# JlinkV9mini.net
KiCad netlist of a schematic drawn in Altium Designer
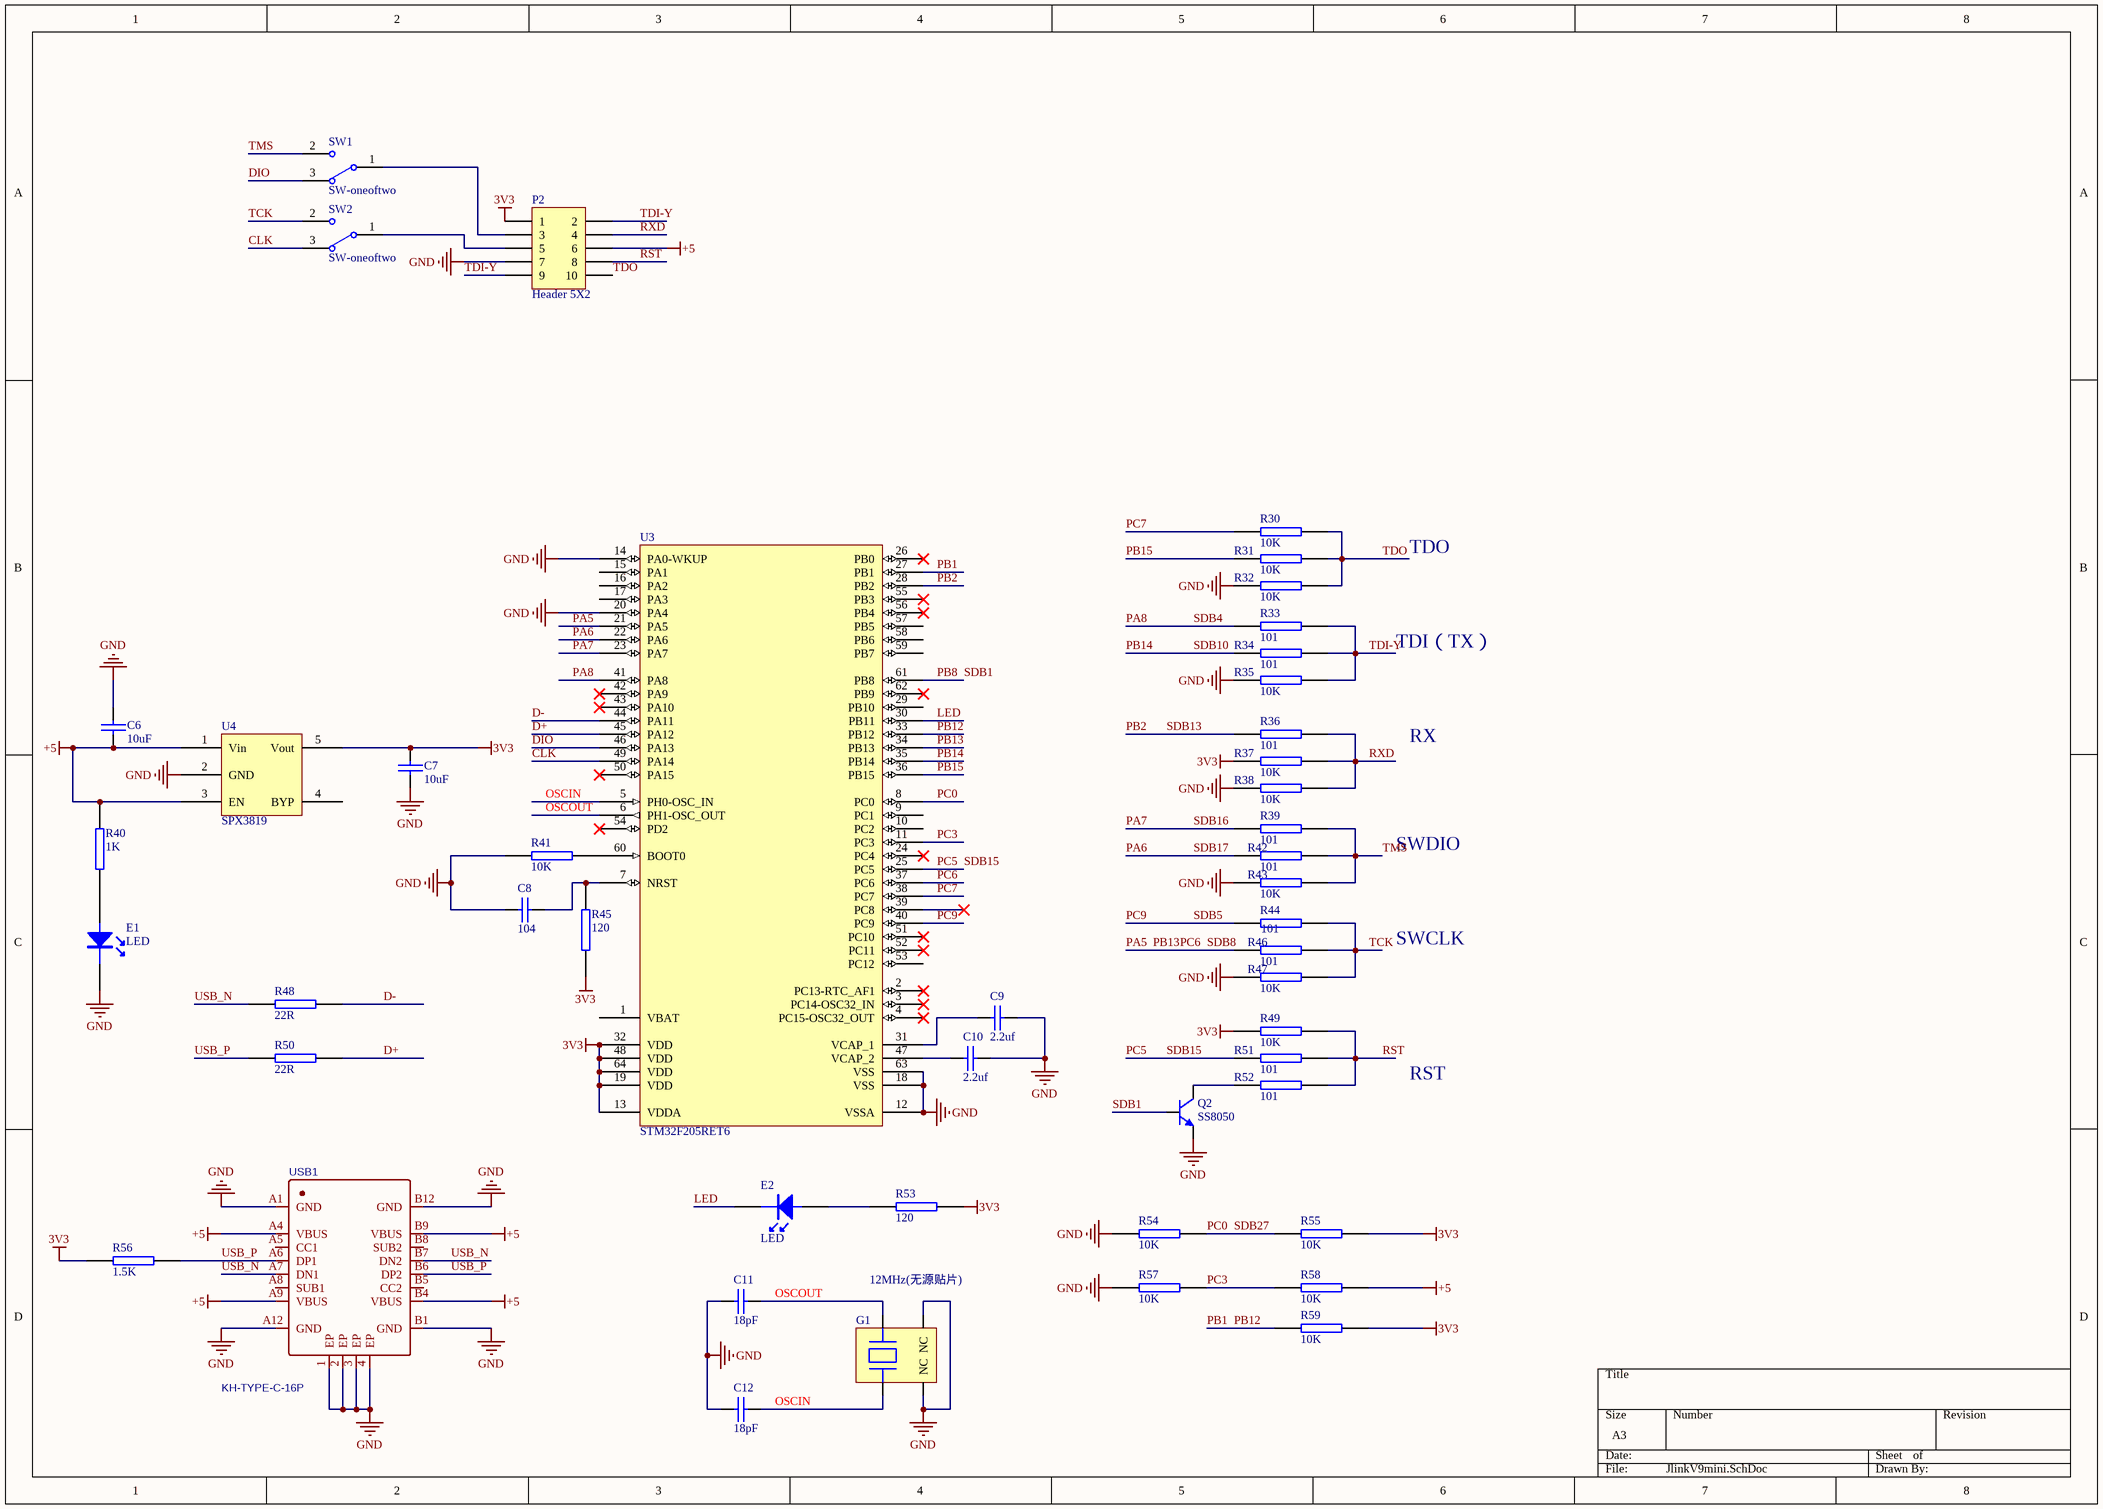
[diagram p0: JlinkV9mini.SchDoc]

(export (version "E")
  (design (tool "Eeschema 10.0.6"))
  (components
    (comp (ref "C6")
      (value "10uF")
      (footprint "0603")
      (description "无极电容")
      (libsource (lib "chenjd") (part "CAP Nonpolarity"))
    )
    (comp (ref "C7")
      (value "10uF")
      (footprint "0603")
      (description "无极电容")
      (libsource (lib "chenjd") (part "CAP Nonpolarity"))
    )
    (comp (ref "C8")
      (value "104")
      (footprint "0603")
      (description "无极电容")
      (libsource (lib "chenjd") (part "CAP Nonpolarity"))
    )
    (comp (ref "C9")
      (value "2.2uf")
      (footprint "0603")
      (description "无极电容")
      (libsource (lib "chenjd") (part "CAP Nonpolarity"))
    )
    (comp (ref "C10")
      (value "2.2uf")
      (footprint "0603")
      (description "无极电容")
      (libsource (lib "chenjd") (part "CAP Nonpolarity"))
    )
    (comp (ref "C11")
      (value "18pF")
      (footprint "0603")
      (description "无极电容")
      (libsource (lib "ZXBC") (part "CAP Nonpolarity"))
    )
    (comp (ref "C12")
      (value "18pF")
      (footprint "0603")
      (description "无极电容")
      (libsource (lib "ZXBC") (part "CAP Nonpolarity"))
    )
    (comp (ref "E1")
      (value "LED")
      (footprint "LED_0603L")
      (description "LED灯")
      (libsource (lib "chenjd") (part "LED"))
    )
    (comp (ref "E2")
      (value "LED")
      (footprint "LED_0603L")
      (description "LED灯")
      (libsource (lib "chenjd") (part "LED"))
    )
    (comp (ref "G1")
      (value "12MHz(无源贴片)")
      (footprint "G3225")
      (description "无源晶振MCU使用")
      (libsource (lib "ZXBC") (part "MM-11B"))
    )
    (comp (ref "P2")
      (value "Header 5X2")
      (footprint "300S-2*5P 2.54MM_2")
      (description "Header, 5-Pin, Dual row")
      (fields (field (name "PUBLISHER") "Altium Limited"))
      (libsource (lib "Miscellaneous Connectors") (part "Header 5X2"))
    )
    (comp (ref "Q2")
      (value "SS8050")
      (footprint "SOT23-3N")
      (description "高频放大-NPN型")
      (fields (field (name "版权归属") "源创客"))
      (libsource (lib "3D库") (part "8050-SMD"))
    )
    (comp (ref "R30")
      (value "10K")
      (footprint "0603")
      (description "电阻")
      (libsource (lib "chenjd") (part "R"))
    )
    (comp (ref "R31")
      (value "10K")
      (footprint "0603")
      (description "电阻")
      (libsource (lib "chenjd") (part "R"))
    )
    (comp (ref "R32")
      (value "10K")
      (footprint "0603")
      (description "电阻")
      (libsource (lib "chenjd") (part "R"))
    )
    (comp (ref "R33")
      (value "101")
      (footprint "0603")
      (description "电阻")
      (libsource (lib "chenjd") (part "R"))
    )
    (comp (ref "R34")
      (value "101")
      (footprint "0603")
      (description "电阻")
      (libsource (lib "chenjd") (part "R"))
    )
    (comp (ref "R35")
      (value "10K")
      (footprint "0603")
      (description "电阻")
      (libsource (lib "chenjd") (part "R"))
    )
    (comp (ref "R36")
      (value "101")
      (footprint "0603")
      (description "电阻")
      (libsource (lib "chenjd") (part "R"))
    )
    (comp (ref "R37")
      (value "10K")
      (footprint "0603")
      (description "电阻")
      (libsource (lib "chenjd") (part "R"))
    )
    (comp (ref "R38")
      (value "10K")
      (footprint "0603")
      (description "电阻")
      (libsource (lib "chenjd") (part "R"))
    )
    (comp (ref "R39")
      (value "101")
      (footprint "0603")
      (description "电阻")
      (libsource (lib "chenjd") (part "R"))
    )
    (comp (ref "R40")
      (value "1K")
      (footprint "0603")
      (description "电阻")
      (libsource (lib "chenjd") (part "R"))
    )
    (comp (ref "R41")
      (value "10K")
      (footprint "0603")
      (description "电阻")
      (libsource (lib "chenjd") (part "R"))
    )
    (comp (ref "R42")
      (value "101")
      (footprint "0603")
      (description "电阻")
      (libsource (lib "chenjd") (part "R"))
    )
    (comp (ref "R43")
      (value "10K")
      (footprint "0603")
      (description "电阻")
      (libsource (lib "chenjd") (part "R"))
    )
    (comp (ref "R44")
      (value "101")
      (footprint "0603")
      (description "电阻")
      (libsource (lib "chenjd") (part "R"))
    )
    (comp (ref "R45")
      (value "120")
      (footprint "0603")
      (description "电阻")
      (libsource (lib "chenjd") (part "R"))
    )
    (comp (ref "R46")
      (value "101")
      (footprint "0603")
      (description "电阻")
      (libsource (lib "chenjd") (part "R"))
    )
    (comp (ref "R47")
      (value "10K")
      (footprint "0603")
      (description "电阻")
      (libsource (lib "chenjd") (part "R"))
    )
    (comp (ref "R48")
      (value "22R")
      (footprint "0603")
      (description "电阻")
      (libsource (lib "chenjd") (part "R"))
    )
    (comp (ref "R49")
      (value "10K")
      (footprint "0603")
      (description "电阻")
      (libsource (lib "chenjd") (part "R"))
    )
    (comp (ref "R50")
      (value "22R")
      (footprint "0603")
      (description "电阻")
      (libsource (lib "chenjd") (part "R"))
    )
    (comp (ref "R51")
      (value "101")
      (footprint "0603")
      (description "电阻")
      (libsource (lib "chenjd") (part "R"))
    )
    (comp (ref "R52")
      (value "101")
      (footprint "0603")
      (description "电阻")
      (libsource (lib "chenjd") (part "R"))
    )
    (comp (ref "R53")
      (value "120")
      (footprint "0603")
      (description "电阻")
      (libsource (lib "chenjd") (part "R"))
    )
    (comp (ref "R54")
      (value "10K")
      (footprint "0603")
      (description "电阻")
      (libsource (lib "chenjd") (part "R"))
    )
    (comp (ref "R55")
      (value "10K")
      (footprint "0603")
      (description "电阻")
      (libsource (lib "chenjd") (part "R"))
    )
    (comp (ref "R56")
      (value "1.5K")
      (footprint "0603")
      (description "电阻")
      (libsource (lib "chenjd") (part "R"))
    )
    (comp (ref "R57")
      (value "10K")
      (footprint "0603")
      (description "电阻")
      (libsource (lib "chenjd") (part "R"))
    )
    (comp (ref "R58")
      (value "10K")
      (footprint "0603")
      (description "电阻")
      (libsource (lib "chenjd") (part "R"))
    )
    (comp (ref "R59")
      (value "10K")
      (footprint "0603")
      (description "电阻")
      (libsource (lib "chenjd") (part "R"))
    )
    (comp (ref "SW1")
      (value "SW-oneoftwo")
      (footprint "SW-oneoftwo-0603")
      (description "二选一电阻开关")
      (libsource (lib "chenjd") (part "SW-oneoftwo"))
    )
    (comp (ref "SW2")
      (value "SW-oneoftwo")
      (footprint "SW-oneoftwo-0603")
      (description "二选一电阻开关")
      (libsource (lib "chenjd") (part "SW-oneoftwo"))
    )
    (comp (ref "U3")
      (value "STM32F205RET6")
      (footprint "LQFP64 10x10_N")
      (description "Microcontroller   ST")
      (libsource (lib "Fantasy") (part "STM32F205RET6"))
    )
    (comp (ref "U4")
      (value "SPX3819")
      (footprint "SOT-23-5")
      (description "稳压器")
      (libsource (lib "chenjd") (part "SPX3819"))
    )
    (comp (ref "USB1")
      (value "KH-TYPE-C-16P")
      (footprint "USB-C-16P")
      (fields (field (name "BOM_SUPPLIER PART") "C709357") (field (name "CONTRIBUTOR") "LCSC"))
      (libsource (lib "chenjd") (part "USB-TYPE-C 16P"))
    )
  )
  (nets
    (net (code "1") (name "+5") (class "Default")
      (node (ref "C6") (pin "2") (pinfunction "2_2") (pintype "passive"))
      (node (ref "P2") (pin "6") (pinfunction "6_6") (pintype "passive"))
      (node (ref "R40") (pin "1") (pinfunction "1_1") (pintype "passive"))
      (node (ref "R58") (pin "2") (pinfunction "2_2") (pintype "passive"))
      (node (ref "U4") (pin "1") (pinfunction "Vin_1") (pintype "passive"))
      (node (ref "U4") (pin "3") (pinfunction "EN_3") (pintype "passive"))
      (node (ref "USB1") (pin "A4") (pinfunction "VBUS_A4") (pintype "passive"))
      (node (ref "USB1") (pin "A9") (pinfunction "VBUS_A9") (pintype "passive"))
      (node (ref "USB1") (pin "B4") (pinfunction "VBUS_B4") (pintype "passive"))
      (node (ref "USB1") (pin "B9") (pinfunction "VBUS_B9") (pintype "passive"))
    )
    (net (code "2") (name "/CLK") (class "Default")
      (node (ref "SW2") (pin "3") (pinfunction "3_3") (pintype "passive"))
      (node (ref "U3") (pin "49") (pinfunction "PA14_49") (pintype "bidirectional"))
    )
    (net (code "3") (name "/D+") (class "Default")
      (node (ref "R50") (pin "1") (pinfunction "1_1") (pintype "passive"))
      (node (ref "U3") (pin "45") (pinfunction "PA12_45") (pintype "bidirectional"))
    )
    (net (code "4") (name "/D-") (class "Default")
      (node (ref "R48") (pin "1") (pinfunction "1_1") (pintype "passive"))
      (node (ref "U3") (pin "44") (pinfunction "PA11_44") (pintype "bidirectional"))
    )
    (net (code "5") (name "/DIO") (class "Default")
      (node (ref "SW1") (pin "3") (pinfunction "3_3") (pintype "passive"))
      (node (ref "U3") (pin "46") (pinfunction "PA13_46") (pintype "bidirectional"))
    )
    (net (code "6") (name "/LED") (class "Default")
      (node (ref "E2") (pin "2") (pinfunction "2_2") (pintype "passive"))
      (node (ref "U3") (pin "30") (pinfunction "PB11_30") (pintype "bidirectional"))
    )
    (net (code "7") (name "/OSCIN") (class "Default")
      (node (ref "C12") (pin "2") (pintype "passive"))
      (node (ref "G1") (pin "1") (pinfunction "1_1") (pintype "passive"))
      (node (ref "U3") (pin "5") (pinfunction "PH0-OSC_IN_5") (pintype "input"))
    )
    (net (code "8") (name "/OSCOUT") (class "Default")
      (node (ref "C11") (pin "2") (pintype "passive"))
      (node (ref "G1") (pin "3") (pinfunction "3_3") (pintype "passive"))
      (node (ref "U3") (pin "6") (pinfunction "PH1-OSC_OUT_6") (pintype "output"))
    )
    (net (code "9") (name "/PA5") (class "Default")
      (node (ref "R46") (pin "1") (pinfunction "1_1") (pintype "passive"))
      (node (ref "U3") (pin "21") (pinfunction "PA5_21") (pintype "bidirectional"))
      (node (ref "U3") (pin "34") (pinfunction "PB13_34") (pintype "bidirectional"))
      (node (ref "U3") (pin "37") (pinfunction "PC6_37") (pintype "bidirectional"))
    )
    (net (code "10") (name "/PA6") (class "Default")
      (node (ref "R42") (pin "1") (pinfunction "1_1") (pintype "passive"))
      (node (ref "U3") (pin "22") (pinfunction "PA6_22") (pintype "bidirectional"))
    )
    (net (code "11") (name "/PA7") (class "Default")
      (node (ref "R39") (pin "1") (pinfunction "1_1") (pintype "passive"))
      (node (ref "U3") (pin "23") (pinfunction "PA7_23") (pintype "bidirectional"))
    )
    (net (code "12") (name "/PA8") (class "Default")
      (node (ref "R33") (pin "1") (pinfunction "1_1") (pintype "passive"))
      (node (ref "U3") (pin "41") (pinfunction "PA8_41") (pintype "bidirectional"))
    )
    (net (code "13") (name "/PB1") (class "Default")
      (node (ref "R59") (pin "1") (pinfunction "1_1") (pintype "passive"))
      (node (ref "U3") (pin "27") (pinfunction "PB1_27") (pintype "bidirectional"))
      (node (ref "U3") (pin "33") (pinfunction "PB12_33") (pintype "bidirectional"))
    )
    (net (code "14") (name "/PB2") (class "Default")
      (node (ref "R36") (pin "1") (pinfunction "1_1") (pintype "passive"))
      (node (ref "U3") (pin "28") (pinfunction "PB2_28") (pintype "bidirectional"))
    )
    (net (code "15") (name "/PB8") (class "Default")
      (node (ref "Q2") (pin "1") (pinfunction "B_1") (pintype "passive"))
      (node (ref "U3") (pin "61") (pinfunction "PB8_61") (pintype "bidirectional"))
    )
    (net (code "16") (name "/PB14") (class "Default")
      (node (ref "R34") (pin "1") (pinfunction "1_1") (pintype "passive"))
      (node (ref "U3") (pin "35") (pinfunction "PB14_35") (pintype "bidirectional"))
    )
    (net (code "17") (name "/PB15") (class "Default")
      (node (ref "R31") (pin "1") (pinfunction "1_1") (pintype "passive"))
      (node (ref "U3") (pin "36") (pinfunction "PB15_36") (pintype "bidirectional"))
    )
    (net (code "18") (name "/PC0") (class "Default")
      (node (ref "R54") (pin "2") (pinfunction "2_2") (pintype "passive"))
      (node (ref "R55") (pin "1") (pinfunction "1_1") (pintype "passive"))
      (node (ref "U3") (pin "8") (pinfunction "PC0_8") (pintype "bidirectional"))
    )
    (net (code "19") (name "/PC3") (class "Default")
      (node (ref "R57") (pin "2") (pinfunction "2_2") (pintype "passive"))
      (node (ref "R58") (pin "1") (pinfunction "1_1") (pintype "passive"))
      (node (ref "U3") (pin "11") (pinfunction "PC3_11") (pintype "bidirectional"))
    )
    (net (code "20") (name "/PC5") (class "Default")
      (node (ref "R51") (pin "1") (pinfunction "1_1") (pintype "passive"))
      (node (ref "U3") (pin "25") (pinfunction "PC5_25") (pintype "bidirectional"))
    )
    (net (code "21") (name "/PC7") (class "Default")
      (node (ref "R30") (pin "1") (pinfunction "1_1") (pintype "passive"))
      (node (ref "U3") (pin "38") (pinfunction "PC7_38") (pintype "bidirectional"))
    )
    (net (code "22") (name "/PC9") (class "Default")
      (node (ref "R44") (pin "1") (pinfunction "1_1") (pintype "passive"))
      (node (ref "U3") (pin "40") (pinfunction "PC9_40") (pintype "bidirectional"))
    )
    (net (code "23") (name "/RST") (class "Default")
      (node (ref "P2") (pin "8") (pinfunction "8_8") (pintype "passive"))
      (node (ref "R49") (pin "2") (pinfunction "2_2") (pintype "passive"))
      (node (ref "R51") (pin "2") (pinfunction "2_2") (pintype "passive"))
      (node (ref "R52") (pin "2") (pinfunction "2_2") (pintype "passive"))
    )
    (net (code "24") (name "/RXD") (class "Default")
      (node (ref "P2") (pin "4") (pinfunction "4_4") (pintype "passive"))
      (node (ref "R36") (pin "2") (pinfunction "2_2") (pintype "passive"))
      (node (ref "R37") (pin "2") (pinfunction "2_2") (pintype "passive"))
      (node (ref "R38") (pin "2") (pinfunction "2_2") (pintype "passive"))
    )
    (net (code "25") (name "/TCK") (class "Default")
      (node (ref "R44") (pin "2") (pinfunction "2_2") (pintype "passive"))
      (node (ref "R46") (pin "2") (pinfunction "2_2") (pintype "passive"))
      (node (ref "R47") (pin "2") (pinfunction "2_2") (pintype "passive"))
      (node (ref "SW2") (pin "2") (pinfunction "2_2") (pintype "passive"))
    )
    (net (code "26") (name "/TDI-Y") (class "Default")
      (node (ref "P2") (pin "2") (pinfunction "2_2") (pintype "passive"))
      (node (ref "P2") (pin "9") (pinfunction "9_9") (pintype "passive"))
      (node (ref "R33") (pin "2") (pinfunction "2_2") (pintype "passive"))
      (node (ref "R34") (pin "2") (pinfunction "2_2") (pintype "passive"))
      (node (ref "R35") (pin "2") (pinfunction "2_2") (pintype "passive"))
    )
    (net (code "27") (name "/TDO") (class "Default")
      (node (ref "P2") (pin "10") (pinfunction "10_10") (pintype "passive"))
      (node (ref "R30") (pin "2") (pinfunction "2_2") (pintype "passive"))
      (node (ref "R31") (pin "2") (pinfunction "2_2") (pintype "passive"))
      (node (ref "R32") (pin "2") (pinfunction "2_2") (pintype "passive"))
    )
    (net (code "28") (name "/TMS") (class "Default")
      (node (ref "R39") (pin "2") (pinfunction "2_2") (pintype "passive"))
      (node (ref "R42") (pin "2") (pinfunction "2_2") (pintype "passive"))
      (node (ref "R43") (pin "2") (pinfunction "2_2") (pintype "passive"))
      (node (ref "SW1") (pin "2") (pinfunction "2_2") (pintype "passive"))
    )
    (net (code "29") (name "/USB_N") (class "Default")
      (node (ref "R48") (pin "2") (pinfunction "2_2") (pintype "passive"))
      (node (ref "USB1") (pin "A7") (pinfunction "DN1_A7") (pintype "passive"))
      (node (ref "USB1") (pin "B7") (pinfunction "DN2_B7") (pintype "passive"))
    )
    (net (code "30") (name "/USB_P") (class "Default")
      (node (ref "R50") (pin "2") (pinfunction "2_2") (pintype "passive"))
      (node (ref "R56") (pin "1") (pinfunction "1_1") (pintype "passive"))
      (node (ref "USB1") (pin "A6") (pinfunction "DP1_A6") (pintype "passive"))
      (node (ref "USB1") (pin "B6") (pinfunction "DP2_B6") (pintype "passive"))
    )
    (net (code "31") (name "3V3") (class "Default")
      (node (ref "C7") (pin "1") (pinfunction "1_1") (pintype "passive"))
      (node (ref "P2") (pin "1") (pinfunction "1_1") (pintype "passive"))
      (node (ref "R37") (pin "1") (pinfunction "1_1") (pintype "passive"))
      (node (ref "R45") (pin "1") (pinfunction "1_1") (pintype "passive"))
      (node (ref "R49") (pin "1") (pinfunction "1_1") (pintype "passive"))
      (node (ref "R53") (pin "2") (pinfunction "2_2") (pintype "passive"))
      (node (ref "R55") (pin "2") (pinfunction "2_2") (pintype "passive"))
      (node (ref "R56") (pin "2") (pinfunction "2_2") (pintype "passive"))
      (node (ref "R59") (pin "2") (pinfunction "2_2") (pintype "passive"))
      (node (ref "U3") (pin "13") (pinfunction "VDDA_13") (pintype "power_in"))
      (node (ref "U3") (pin "19") (pinfunction "VDD_19") (pintype "power_in"))
      (node (ref "U3") (pin "32") (pinfunction "VDD_32") (pintype "power_in"))
      (node (ref "U3") (pin "48") (pinfunction "VDD_48") (pintype "power_in"))
      (node (ref "U3") (pin "64") (pinfunction "VDD_64") (pintype "power_in"))
      (node (ref "U4") (pin "5") (pinfunction "Vout_5") (pintype "passive"))
    )
    (net (code "32") (name "GND") (class "Default")
      (node (ref "C10") (pin "2") (pinfunction "2_2") (pintype "passive"))
      (node (ref "C11") (pin "1") (pintype "passive"))
      (node (ref "C12") (pin "1") (pintype "passive"))
      (node (ref "C6") (pin "1") (pinfunction "1_1") (pintype "passive"))
      (node (ref "C7") (pin "2") (pinfunction "2_2") (pintype "passive"))
      (node (ref "C8") (pin "1") (pinfunction "1_1") (pintype "passive"))
      (node (ref "C9") (pin "2") (pinfunction "2_2") (pintype "passive"))
      (node (ref "E1") (pin "2") (pinfunction "2_2") (pintype "passive"))
      (node (ref "G1") (pin "2") (pinfunction "NC_2") (pintype "passive"))
      (node (ref "G1") (pin "4") (pinfunction "NC_4") (pintype "passive"))
      (node (ref "P2") (pin "7") (pinfunction "7_7") (pintype "passive"))
      (node (ref "Q2") (pin "2") (pinfunction "E_2") (pintype "passive"))
      (node (ref "R32") (pin "1") (pinfunction "1_1") (pintype "passive"))
      (node (ref "R35") (pin "1") (pinfunction "1_1") (pintype "passive"))
      (node (ref "R38") (pin "1") (pinfunction "1_1") (pintype "passive"))
      (node (ref "R41") (pin "1") (pinfunction "1_1") (pintype "passive"))
      (node (ref "R43") (pin "1") (pinfunction "1_1") (pintype "passive"))
      (node (ref "R47") (pin "1") (pinfunction "1_1") (pintype "passive"))
      (node (ref "R54") (pin "1") (pinfunction "1_1") (pintype "passive"))
      (node (ref "R57") (pin "1") (pinfunction "1_1") (pintype "passive"))
      (node (ref "U3") (pin "12") (pinfunction "VSSA_12") (pintype "power_in"))
      (node (ref "U3") (pin "14") (pinfunction "PA0-WKUP_14") (pintype "bidirectional"))
      (node (ref "U3") (pin "18") (pinfunction "VSS_18") (pintype "power_in"))
      (node (ref "U3") (pin "20") (pinfunction "PA4_20") (pintype "bidirectional"))
      (node (ref "U3") (pin "63") (pinfunction "VSS_63") (pintype "power_in"))
      (node (ref "U4") (pin "2") (pinfunction "GND_2") (pintype "passive"))
      (node (ref "USB1") (pin "1") (pinfunction "EP_1") (pintype "passive"))
      (node (ref "USB1") (pin "2") (pinfunction "EP_2") (pintype "passive"))
      (node (ref "USB1") (pin "3") (pinfunction "EP_3") (pintype "passive"))
      (node (ref "USB1") (pin "4") (pinfunction "EP_4") (pintype "passive"))
      (node (ref "USB1") (pin "A1") (pinfunction "GND_A1") (pintype "passive"))
      (node (ref "USB1") (pin "A12") (pinfunction "GND_A12") (pintype "passive"))
      (node (ref "USB1") (pin "B1") (pinfunction "GND_B1") (pintype "passive"))
      (node (ref "USB1") (pin "B12") (pinfunction "GND_B12") (pintype "passive"))
    )
    (net (code "33") (name "Net-(E1-Pad1)") (class "Default")
      (node (ref "E1") (pin "1") (pinfunction "1_1") (pintype "passive"))
      (node (ref "R40") (pin "2") (pinfunction "2_2") (pintype "passive"))
    )
    (net (code "34") (name "Net-(E2-Pad1)") (class "Default")
      (node (ref "E2") (pin "1") (pinfunction "1_1") (pintype "passive"))
      (node (ref "R53") (pin "1") (pinfunction "1_1") (pintype "passive"))
    )
    (net (code "35") (name "Net-(P2-Pad3)") (class "Default")
      (node (ref "P2") (pin "3") (pinfunction "3_3") (pintype "passive"))
      (node (ref "SW1") (pin "1") (pinfunction "1_1") (pintype "passive"))
    )
    (net (code "36") (name "Net-(P2-Pad5)") (class "Default")
      (node (ref "P2") (pin "5") (pinfunction "5_5") (pintype "passive"))
      (node (ref "SW2") (pin "1") (pinfunction "1_1") (pintype "passive"))
    )
    (net (code "37") (name "Net-(Q2-C)") (class "Default")
      (node (ref "Q2") (pin "3") (pinfunction "C_3") (pintype "passive"))
      (node (ref "R52") (pin "1") (pinfunction "1_1") (pintype "passive"))
    )
    (net (code "38") (name "Net-(U3-BOOT0)") (class "Default")
      (node (ref "R41") (pin "2") (pinfunction "2_2") (pintype "passive"))
      (node (ref "U3") (pin "60") (pinfunction "BOOT0_60") (pintype "input"))
    )
    (net (code "39") (name "Net-(U3-NRST)") (class "Default")
      (node (ref "C8") (pin "2") (pinfunction "2_2") (pintype "passive"))
      (node (ref "R45") (pin "2") (pinfunction "2_2") (pintype "passive"))
      (node (ref "U3") (pin "7") (pinfunction "NRST_7") (pintype "bidirectional"))
    )
    (net (code "40") (name "Net-(U3-VCAP_1)") (class "Default")
      (node (ref "C9") (pin "1") (pinfunction "1_1") (pintype "passive"))
      (node (ref "U3") (pin "31") (pinfunction "VCAP_1_31") (pintype "power_in"))
    )
    (net (code "41") (name "Net-(U3-VCAP_2)") (class "Default")
      (node (ref "C10") (pin "1") (pinfunction "1_1") (pintype "passive"))
      (node (ref "U3") (pin "47") (pinfunction "VCAP_2_47") (pintype "power_in"))
    )
    (net (code "42") (name "unconnected-(U3-PA1-Pad15)") (class "Default")
      (node (ref "U3") (pin "15") (pinfunction "PA1_15") (pintype "bidirectional"))
    )
    (net (code "43") (name "unconnected-(U3-PA2-Pad16)") (class "Default")
      (node (ref "U3") (pin "16") (pinfunction "PA2_16") (pintype "bidirectional"))
    )
    (net (code "44") (name "unconnected-(U3-PA3-Pad17)") (class "Default")
      (node (ref "U3") (pin "17") (pinfunction "PA3_17") (pintype "bidirectional"))
    )
    (net (code "45") (name "unconnected-(U3-PA9-Pad42)") (class "Default")
      (node (ref "U3") (pin "42") (pinfunction "PA9_42") (pintype "bidirectional+no_connect"))
    )
    (net (code "46") (name "unconnected-(U3-PA10-Pad43)") (class "Default")
      (node (ref "U3") (pin "43") (pinfunction "PA10_43") (pintype "bidirectional+no_connect"))
    )
    (net (code "47") (name "unconnected-(U3-PA15-Pad50)") (class "Default")
      (node (ref "U3") (pin "50") (pinfunction "PA15_50") (pintype "bidirectional+no_connect"))
    )
    (net (code "48") (name "unconnected-(U3-PB0-Pad26)") (class "Default")
      (node (ref "U3") (pin "26") (pinfunction "PB0_26") (pintype "bidirectional+no_connect"))
    )
    (net (code "49") (name "unconnected-(U3-PB3-Pad55)") (class "Default")
      (node (ref "U3") (pin "55") (pinfunction "PB3_55") (pintype "bidirectional+no_connect"))
    )
    (net (code "50") (name "unconnected-(U3-PB4-Pad56)") (class "Default")
      (node (ref "U3") (pin "56") (pinfunction "PB4_56") (pintype "bidirectional+no_connect"))
    )
    (net (code "51") (name "unconnected-(U3-PB5-Pad57)") (class "Default")
      (node (ref "U3") (pin "57") (pinfunction "PB5_57") (pintype "bidirectional"))
    )
    (net (code "52") (name "unconnected-(U3-PB6-Pad58)") (class "Default")
      (node (ref "U3") (pin "58") (pinfunction "PB6_58") (pintype "bidirectional"))
    )
    (net (code "53") (name "unconnected-(U3-PB7-Pad59)") (class "Default")
      (node (ref "U3") (pin "59") (pinfunction "PB7_59") (pintype "bidirectional"))
    )
    (net (code "54") (name "unconnected-(U3-PB9-Pad62)") (class "Default")
      (node (ref "U3") (pin "62") (pinfunction "PB9_62") (pintype "bidirectional+no_connect"))
    )
    (net (code "55") (name "unconnected-(U3-PB10-Pad29)") (class "Default")
      (node (ref "U3") (pin "29") (pinfunction "PB10_29") (pintype "bidirectional"))
    )
    (net (code "56") (name "unconnected-(U3-PC1-Pad9)") (class "Default")
      (node (ref "U3") (pin "9") (pinfunction "PC1_9") (pintype "bidirectional"))
    )
    (net (code "57") (name "unconnected-(U3-PC2-Pad10)") (class "Default")
      (node (ref "U3") (pin "10") (pinfunction "PC2_10") (pintype "bidirectional"))
    )
    (net (code "58") (name "unconnected-(U3-PC4-Pad24)") (class "Default")
      (node (ref "U3") (pin "24") (pinfunction "PC4_24") (pintype "bidirectional+no_connect"))
    )
    (net (code "59") (name "unconnected-(U3-PC8-Pad39)") (class "Default")
      (node (ref "U3") (pin "39") (pinfunction "PC8_39") (pintype "bidirectional+no_connect"))
    )
    (net (code "60") (name "unconnected-(U3-PC10-Pad51)") (class "Default")
      (node (ref "U3") (pin "51") (pinfunction "PC10_51") (pintype "bidirectional+no_connect"))
    )
    (net (code "61") (name "unconnected-(U3-PC11-Pad52)") (class "Default")
      (node (ref "U3") (pin "52") (pinfunction "PC11_52") (pintype "bidirectional+no_connect"))
    )
    (net (code "62") (name "unconnected-(U3-PC12-Pad53)") (class "Default")
      (node (ref "U3") (pin "53") (pinfunction "PC12_53") (pintype "bidirectional"))
    )
    (net (code "63") (name "unconnected-(U3-PC13-RTC_AF1-Pad2)") (class "Default")
      (node (ref "U3") (pin "2") (pinfunction "PC13-RTC_AF1_2") (pintype "bidirectional+no_connect"))
    )
    (net (code "64") (name "unconnected-(U3-PC14-OSC32_IN-Pad3)") (class "Default")
      (node (ref "U3") (pin "3") (pinfunction "PC14-OSC32_IN_3") (pintype "bidirectional+no_connect"))
    )
    (net (code "65") (name "unconnected-(U3-PC15-OSC32_OUT-Pad4)") (class "Default")
      (node (ref "U3") (pin "4") (pinfunction "PC15-OSC32_OUT_4") (pintype "bidirectional+no_connect"))
    )
    (net (code "66") (name "unconnected-(U3-PD2-Pad54)") (class "Default")
      (node (ref "U3") (pin "54") (pinfunction "PD2_54") (pintype "bidirectional+no_connect"))
    )
    (net (code "67") (name "unconnected-(U3-VBAT-Pad1)") (class "Default")
      (node (ref "U3") (pin "1") (pinfunction "VBAT_1") (pintype "power_in"))
    )
    (net (code "68") (name "unconnected-(U4-BYP-Pad4)") (class "Default")
      (node (ref "U4") (pin "4") (pinfunction "BYP_4") (pintype "passive"))
    )
    (net (code "69") (name "unconnected-(USB1-CC1-PadA5)") (class "Default")
      (node (ref "USB1") (pin "A5") (pinfunction "CC1_A5") (pintype "passive"))
    )
    (net (code "70") (name "unconnected-(USB1-CC2-PadB5)") (class "Default")
      (node (ref "USB1") (pin "B5") (pinfunction "CC2_B5") (pintype "passive"))
    )
    (net (code "71") (name "unconnected-(USB1-SUB1-PadA8)") (class "Default")
      (node (ref "USB1") (pin "A8") (pinfunction "SUB1_A8") (pintype "passive"))
    )
    (net (code "72") (name "unconnected-(USB1-SUB2-PadB8)") (class "Default")
      (node (ref "USB1") (pin "B8") (pinfunction "SUB2_B8") (pintype "passive"))
    )
  )
)
